# MCU.net
KiCad netlist of a schematic drawn in Altium Designer
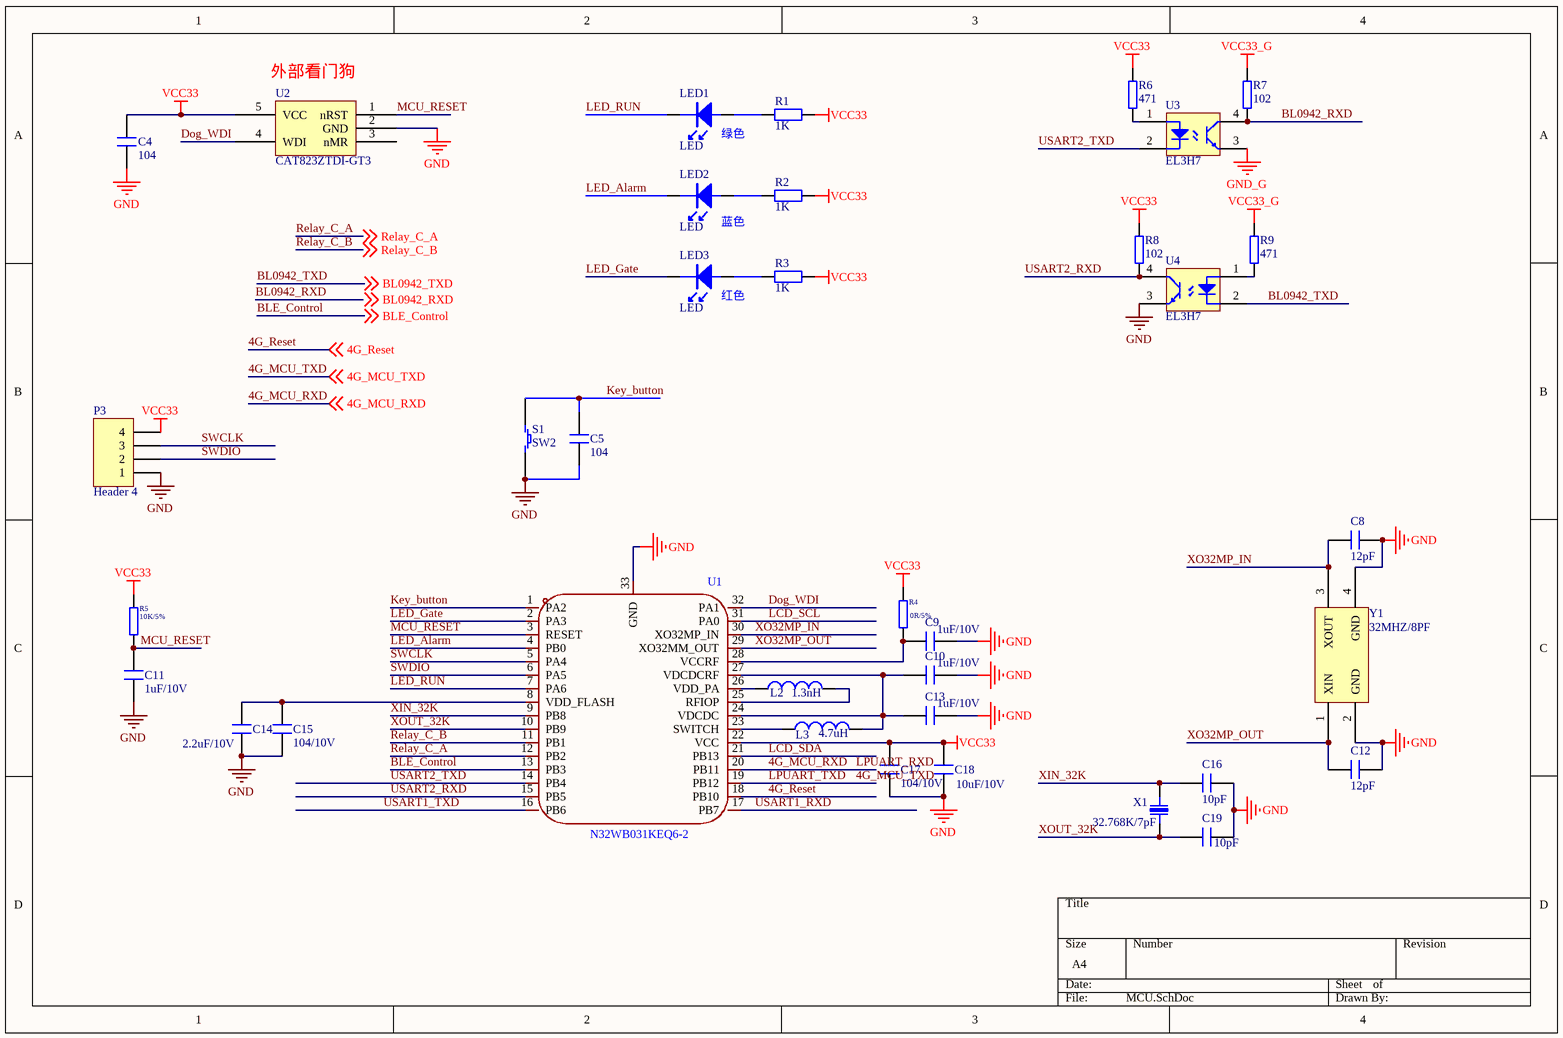
[diagram p0: MCU.SchDoc]

(export (version "E")
  (design (tool "Eeschema 10.0.6"))
  (components
    (comp (ref "C4") (value "104") (footprint "0603R") (libsource (lib "ES_Schematic") (part "CAP")))
    (comp (ref "C5") (value "104") (footprint "0603R") (libsource (lib "ES_Schematic") (part "CAP")))
    (comp (ref "C8") (value "12pF") (footprint "0603r") (libsource (lib "ES_Schematic") (part "CAP")))
    (comp (ref "C9") (value "1uF/10V") (footprint "0603R") (libsource (lib "ES_Schematic") (part "CAP_1")))
    (comp (ref "C10") (value "1uF/10V") (footprint "0603R") (libsource (lib "ES_Schematic") (part "CAP_1")))
    (comp (ref "C11") (value "1uF/10V") (footprint "0603R") (libsource (lib "ES_Schematic") (part "CAP_1")))
    (comp (ref "C12") (value "12pF") (footprint "0603r") (libsource (lib "ES_Schematic") (part "CAP")))
    (comp (ref "C13") (value "1uF/10V") (footprint "0603R") (libsource (lib "ES_Schematic") (part "CAP_1")))
    (comp (ref "C14") (value "2.2uF/10V") (footprint "0603R") (libsource (lib "ES_Schematic") (part "CAP_1")))
    (comp (ref "C15") (value "104/10V") (footprint "0603R") (libsource (lib "ES_Schematic") (part "CAP_1")))
    (comp (ref "C16") (value "10pF") (footprint "0603r") (libsource (lib "ES_Schematic") (part "CAP")))
    (comp (ref "C17") (value "104/10V") (footprint "0603R") (libsource (lib "ES_Schematic") (part "CAP_1")))
    (comp (ref "C18") (value "10uF/10V") (footprint "0603R") (libsource (lib "ES_Schematic") (part "CAP_1")))
    (comp (ref "C19") (value "10pF") (footprint "0603r") (libsource (lib "ES_Schematic") (part "CAP")))
    (comp (ref "L2")
      (value "1.3nH")
      (footprint "0603R")
      (description "Inductor")
      (fields (field (name "PUBLISHER") "Altium Limited"))
      (libsource (lib "Miscellaneous Devices") (part "Inductor"))
    )
    (comp (ref "L3")
      (value "4.7uH")
      (footprint "0603R")
      (description "Inductor")
      (fields (field (name "PUBLISHER") "Altium Limited"))
      (libsource (lib "Miscellaneous Devices") (part "Inductor"))
    )
    (comp (ref "LED1") (value "LED") (footprint "LED0805") (libsource (lib "ES_Schematic") (part "LED")))
    (comp (ref "LED2") (value "LED") (footprint "LED0805") (libsource (lib "ES_Schematic") (part "LED")))
    (comp (ref "LED3") (value "LED") (footprint "LED0805") (libsource (lib "ES_Schematic") (part "LED")))
    (comp (ref "P3")
      (value "Header 4")
      (footprint "HDR1X4")
      (description "Header, 4-Pin")
      (fields (field (name "PUBLISHER") "Altium Limited"))
      (libsource (lib "Miscellaneous Connectors") (part "Header 4"))
    )
    (comp (ref "R1")
      (value "1K")
      (footprint "0603R")
      (fields (field (name "Comment") "Res2") (field (name "PUBLISHER") "Altium Limited"))
      (libsource (lib "Miscellaneous Devices") (part "Res2"))
    )
    (comp (ref "R2")
      (value "1K")
      (footprint "0603R")
      (fields (field (name "Comment") "Res2") (field (name "PUBLISHER") "Altium Limited"))
      (libsource (lib "Miscellaneous Devices") (part "Res2"))
    )
    (comp (ref "R3")
      (value "1K")
      (footprint "0603R")
      (fields (field (name "Comment") "Res2") (field (name "PUBLISHER") "Altium Limited"))
      (libsource (lib "Miscellaneous Devices") (part "Res2"))
    )
    (comp (ref "R4") (value "0R/5%") (footprint "0603R") (libsource (lib "ES_Schematic") (part "RES")))
    (comp (ref "R5") (value "10K/5%") (footprint "0603R") (libsource (lib "ES_Schematic") (part "RES")))
    (comp (ref "R6") (value "471") (footprint "0603R") (libsource (lib "ES_Schematic") (part "RES")))
    (comp (ref "R7") (value "102") (footprint "0603R") (libsource (lib "ES_Schematic") (part "RES")))
    (comp (ref "R8") (value "102") (footprint "0603R") (libsource (lib "ES_Schematic") (part "RES")))
    (comp (ref "R9") (value "471") (footprint "0603R") (libsource (lib "ES_Schematic") (part "RES")))
    (comp (ref "S1")
      (value "SW2")
      (footprint "4.5*4.5贴片4脚独立按键")
      (libsource (lib "ES_Schematic") (part "SW2"))
    )
    (comp (ref "U1")
      (value "N32WB031KEQ6-2")
      (footprint "QFN-32_L4.0-W4.0-P0.40-TL-EP2.8")
      (fields (field (name "MANUFACTURER") "Nations(国民技术)"))
      (libsource (lib "altium-import") (part "root_0_N32WB031KEQ6-2_"))
    )
    (comp (ref "U2")
      (value "CAT823ZTDI-GT3")
      (footprint "SOT-23-5")
      (libsource (lib "ES_Schematic") (part "CAT823"))
    )
    (comp (ref "U3")
      (value "EL3H7")
      (footprint "EL3H7")
      (libsource (lib "ES_Schematic") (part "Optical_Coupler_1"))
    )
    (comp (ref "U4") (value "EL3H7") (footprint "EL3H7") (libsource (lib "") (part "Optical_Coupler_1_1")))
    (comp (ref "X1") (value "32.768K/7pF") (footprint "Y3215") (libsource (lib "ES_Schematic") (part "XTAL")))
    (comp (ref "Y1") (value "32MHZ/8PF") (footprint "3225") (libsource (lib "others") (part "12MHz无源")))
  )
  (nets
    (net (code "1") (name "/Dog_WDI") (class "Default")
      (node (ref "U1") (pin "32") (pinfunction "PA1_32") (pintype "passive"))
      (node (ref "U2") (pin "4") (pinfunction "WDI_4") (pintype "passive"))
    )
    (net (code "2") (name "/Key_button") (class "Default")
      (node (ref "C5") (pin "1") (pinfunction "1_1") (pintype "passive"))
      (node (ref "S1") (pin "1") (pinfunction "1_1") (pintype "passive"))
      (node (ref "U1") (pin "1") (pinfunction "PA2_1") (pintype "passive"))
    )
    (net (code "3") (name "/LCD_SCL") (class "Default")
      (node (ref "U1") (pin "31") (pinfunction "PA0_31") (pintype "passive"))
    )
    (net (code "4") (name "/LCD_SDA") (class "Default")
      (node (ref "U1") (pin "21") (pinfunction "PB13_21") (pintype "passive"))
    )
    (net (code "5") (name "/LED_Alarm") (class "Default")
      (node (ref "LED2") (pin "2") (pinfunction "2_2") (pintype "passive"))
      (node (ref "U1") (pin "4") (pinfunction "PB0_4") (pintype "passive"))
    )
    (net (code "6") (name "/LED_Gate") (class "Default")
      (node (ref "LED3") (pin "2") (pinfunction "2_2") (pintype "passive"))
      (node (ref "U1") (pin "2") (pinfunction "PA3_2") (pintype "passive"))
    )
    (net (code "7") (name "/LED_RUN") (class "Default")
      (node (ref "LED1") (pin "2") (pinfunction "2_2") (pintype "passive"))
      (node (ref "U1") (pin "7") (pinfunction "PA6_7") (pintype "passive"))
    )
    (net (code "8") (name "/MCU_RESET") (class "Default")
      (node (ref "C11") (pin "2") (pinfunction "2_2") (pintype "passive"))
      (node (ref "R5") (pin "2") (pinfunction "2_2") (pintype "passive"))
      (node (ref "U1") (pin "3") (pinfunction "RESET_3") (pintype "passive"))
      (node (ref "U2") (pin "1") (pinfunction "nRST_1") (pintype "passive"))
    )
    (net (code "9") (name "/SWCLK") (class "Default")
      (node (ref "P3") (pin "3") (pinfunction "3_3") (pintype "passive"))
      (node (ref "U1") (pin "5") (pinfunction "PA4_5") (pintype "passive"))
    )
    (net (code "10") (name "/SWDIO") (class "Default")
      (node (ref "P3") (pin "2") (pinfunction "2_2") (pintype "passive"))
      (node (ref "U1") (pin "6") (pinfunction "PA5_6") (pintype "passive"))
    )
    (net (code "11") (name "/USART1_RXD") (class "Default")
      (node (ref "U1") (pin "17") (pinfunction "PB7_17") (pintype "passive"))
    )
    (net (code "12") (name "/USART1_TXD") (class "Default")
      (node (ref "U1") (pin "16") (pinfunction "PB6_16") (pintype "passive"))
    )
    (net (code "13") (name "/USART2_RXD") (class "Default")
      (node (ref "R8") (pin "1") (pinfunction "1_1") (pintype "passive"))
      (node (ref "U1") (pin "15") (pinfunction "PB5_15") (pintype "passive"))
      (node (ref "U4") (pin "4") (pinfunction "C_4") (pintype "passive"))
    )
    (net (code "14") (name "/USART2_TXD") (class "Default")
      (node (ref "U1") (pin "14") (pinfunction "PB4_14") (pintype "passive"))
      (node (ref "U3") (pin "2") (pinfunction "K_2") (pintype "passive"))
    )
    (net (code "15") (name "/XIN_32K") (class "Default")
      (node (ref "C16") (pin "1") (pinfunction "1_1") (pintype "passive"))
      (node (ref "U1") (pin "9") (pinfunction "PB8_9") (pintype "passive"))
      (node (ref "X1") (pin "2") (pinfunction "2_2") (pintype "passive"))
    )
    (net (code "16") (name "/XO32MP_IN") (class "Default")
      (node (ref "C8") (pin "2") (pinfunction "2_2") (pintype "passive"))
      (node (ref "U1") (pin "30") (pinfunction "XO32MP_IN_30") (pintype "passive"))
      (node (ref "Y1") (pin "3") (pinfunction "XOUT_3") (pintype "passive"))
    )
    (net (code "17") (name "/XO32MP_OUT") (class "Default")
      (node (ref "C12") (pin "2") (pinfunction "2_2") (pintype "passive"))
      (node (ref "U1") (pin "29") (pinfunction "XO32MM_OUT_29") (pintype "passive"))
      (node (ref "Y1") (pin "1") (pinfunction "XIN_1") (pintype "passive"))
    )
    (net (code "18") (name "/XOUT_32K") (class "Default")
      (node (ref "C19") (pin "2") (pinfunction "2_2") (pintype "passive"))
      (node (ref "U1") (pin "10") (pinfunction "PB9_10") (pintype "passive"))
      (node (ref "X1") (pin "1") (pinfunction "1_1") (pintype "passive"))
    )
    (net (code "19") (name "4G_MCU_RXD") (class "Default")
      (node (ref "U1") (pin "20") (pinfunction "PB11_20") (pintype "passive"))
    )
    (net (code "20") (name "4G_MCU_TXD") (class "Default")
      (node (ref "U1") (pin "19") (pinfunction "PB12_19") (pintype "passive"))
    )
    (net (code "21") (name "4G_Reset") (class "Default")
      (node (ref "U1") (pin "18") (pinfunction "PB10_18") (pintype "passive"))
    )
    (net (code "22") (name "BL0942_RXD") (class "Default")
      (node (ref "R7") (pin "1") (pinfunction "1_1") (pintype "passive"))
      (node (ref "U3") (pin "4") (pinfunction "C_4") (pintype "passive"))
    )
    (net (code "23") (name "BL0942_TXD") (class "Default")
      (node (ref "U4") (pin "2") (pinfunction "K_2") (pintype "passive"))
    )
    (net (code "24") (name "BLE_Control") (class "Default")
      (node (ref "U1") (pin "13") (pinfunction "PB3_13") (pintype "passive"))
    )
    (net (code "25") (name "GND") (class "Default")
      (node (ref "C10") (pin "1") (pinfunction "1_1") (pintype "passive"))
      (node (ref "C11") (pin "1") (pinfunction "1_1") (pintype "passive"))
      (node (ref "C12") (pin "1") (pinfunction "1_1") (pintype "passive"))
      (node (ref "C13") (pin "1") (pinfunction "1_1") (pintype "passive"))
      (node (ref "C14") (pin "1") (pinfunction "1_1") (pintype "passive"))
      (node (ref "C15") (pin "1") (pinfunction "1_1") (pintype "passive"))
      (node (ref "C16") (pin "2") (pinfunction "2_2") (pintype "passive"))
      (node (ref "C17") (pin "1") (pinfunction "1_1") (pintype "passive"))
      (node (ref "C18") (pin "1") (pinfunction "1_1") (pintype "passive"))
      (node (ref "C19") (pin "1") (pinfunction "1_1") (pintype "passive"))
      (node (ref "C4") (pin "1") (pinfunction "1_1") (pintype "passive"))
      (node (ref "C5") (pin "2") (pinfunction "2_2") (pintype "passive"))
      (node (ref "C8") (pin "1") (pinfunction "1_1") (pintype "passive"))
      (node (ref "C9") (pin "1") (pinfunction "1_1") (pintype "passive"))
      (node (ref "P3") (pin "1") (pinfunction "1_1") (pintype "passive"))
      (node (ref "S1") (pin "2") (pinfunction "2_2") (pintype "passive"))
      (node (ref "U1") (pin "33") (pinfunction "GND_33") (pintype "passive"))
      (node (ref "U2") (pin "2") (pinfunction "GND_2") (pintype "passive"))
      (node (ref "U4") (pin "3") (pinfunction "E_3") (pintype "passive"))
      (node (ref "Y1") (pin "2") (pinfunction "GND_2") (pintype "passive"))
      (node (ref "Y1") (pin "4") (pinfunction "GND_4") (pintype "passive"))
    )
    (net (code "26") (name "GND_G") (class "Default")
      (node (ref "U3") (pin "3") (pinfunction "E_3") (pintype "passive"))
    )
    (net (code "27") (name "Net-(LED1-Pad1)") (class "Default")
      (node (ref "LED1") (pin "1") (pinfunction "1_1") (pintype "passive"))
      (node (ref "R1") (pin "2") (pinfunction "2_2") (pintype "passive"))
    )
    (net (code "28") (name "Net-(LED2-Pad1)") (class "Default")
      (node (ref "LED2") (pin "1") (pinfunction "1_1") (pintype "passive"))
      (node (ref "R2") (pin "2") (pinfunction "2_2") (pintype "passive"))
    )
    (net (code "29") (name "Net-(LED3-Pad1)") (class "Default")
      (node (ref "LED3") (pin "1") (pinfunction "1_1") (pintype "passive"))
      (node (ref "R3") (pin "2") (pinfunction "2_2") (pintype "passive"))
    )
    (net (code "30") (name "Net-(U1-RFIOP)") (class "Default")
      (node (ref "L2") (pin "2") (pinfunction "2_2") (pintype "passive"))
      (node (ref "U1") (pin "25") (pinfunction "RFIOP_25") (pintype "passive"))
    )
    (net (code "31") (name "Net-(U1-SWITCH)") (class "Default")
      (node (ref "L3") (pin "1") (pinfunction "1_1") (pintype "passive"))
      (node (ref "U1") (pin "23") (pinfunction "SWITCH_23") (pintype "passive"))
    )
    (net (code "32") (name "Net-(U1-VCCRF)") (class "Default")
      (node (ref "C9") (pin "2") (pinfunction "2_2") (pintype "passive"))
      (node (ref "R4") (pin "2") (pinfunction "2_2") (pintype "passive"))
      (node (ref "U1") (pin "28") (pinfunction "VCCRF_28") (pintype "passive"))
    )
    (net (code "33") (name "Net-(U1-VDCDC)") (class "Default")
      (node (ref "C10") (pin "2") (pinfunction "2_2") (pintype "passive"))
      (node (ref "C13") (pin "2") (pinfunction "2_2") (pintype "passive"))
      (node (ref "L3") (pin "2") (pinfunction "2_2") (pintype "passive"))
      (node (ref "U1") (pin "24") (pinfunction "VDCDC_24") (pintype "passive"))
      (node (ref "U1") (pin "27") (pinfunction "VDCDCRF_27") (pintype "passive"))
    )
    (net (code "34") (name "Net-(U1-VDD_FLASH)") (class "Default")
      (node (ref "C14") (pin "2") (pinfunction "2_2") (pintype "passive"))
      (node (ref "C15") (pin "2") (pinfunction "2_2") (pintype "passive"))
      (node (ref "U1") (pin "8") (pinfunction "VDD_FLASH_8") (pintype "passive"))
    )
    (net (code "35") (name "Net-(U1-VDD_PA)") (class "Default")
      (node (ref "L2") (pin "1") (pinfunction "1_1") (pintype "passive"))
      (node (ref "U1") (pin "26") (pinfunction "VDD_PA_26") (pintype "passive"))
    )
    (net (code "36") (name "Net-(U3-A)") (class "Default")
      (node (ref "R6") (pin "2") (pinfunction "2_2") (pintype "passive"))
      (node (ref "U3") (pin "1") (pinfunction "A_1") (pintype "passive"))
    )
    (net (code "37") (name "Net-(U4-A)") (class "Default")
      (node (ref "R9") (pin "2") (pinfunction "2_2") (pintype "passive"))
      (node (ref "U4") (pin "1") (pinfunction "A_1") (pintype "passive"))
    )
    (net (code "38") (name "Relay_C_A") (class "Default")
      (node (ref "U1") (pin "12") (pinfunction "PB2_12") (pintype "passive"))
    )
    (net (code "39") (name "Relay_C_B") (class "Default")
      (node (ref "U1") (pin "11") (pinfunction "PB1_11") (pintype "passive"))
    )
    (net (code "40") (name "VCC33") (class "Default")
      (node (ref "C17") (pin "2") (pinfunction "2_2") (pintype "passive"))
      (node (ref "C18") (pin "2") (pinfunction "2_2") (pintype "passive"))
      (node (ref "C4") (pin "2") (pinfunction "2_2") (pintype "passive"))
      (node (ref "P3") (pin "4") (pinfunction "4_4") (pintype "passive"))
      (node (ref "R1") (pin "1") (pinfunction "1_1") (pintype "passive"))
      (node (ref "R2") (pin "1") (pinfunction "1_1") (pintype "passive"))
      (node (ref "R3") (pin "1") (pinfunction "1_1") (pintype "passive"))
      (node (ref "R4") (pin "1") (pinfunction "1_1") (pintype "passive"))
      (node (ref "R5") (pin "1") (pinfunction "1_1") (pintype "passive"))
      (node (ref "R6") (pin "1") (pinfunction "1_1") (pintype "passive"))
      (node (ref "R8") (pin "2") (pinfunction "2_2") (pintype "passive"))
      (node (ref "U1") (pin "22") (pinfunction "VCC_22") (pintype "passive"))
      (node (ref "U2") (pin "5") (pinfunction "VCC_5") (pintype "passive"))
    )
    (net (code "41") (name "VCC33_G") (class "Default")
      (node (ref "R7") (pin "2") (pinfunction "2_2") (pintype "passive"))
      (node (ref "R9") (pin "1") (pinfunction "1_1") (pintype "passive"))
    )
    (net (code "42") (name "unconnected-(U2-nMR-Pad3)") (class "Default")
      (node (ref "U2") (pin "3") (pinfunction "nMR_3") (pintype "passive"))
    )
  )
)
